# 24V.net
KiCad netlist of a schematic drawn in Altium Designer
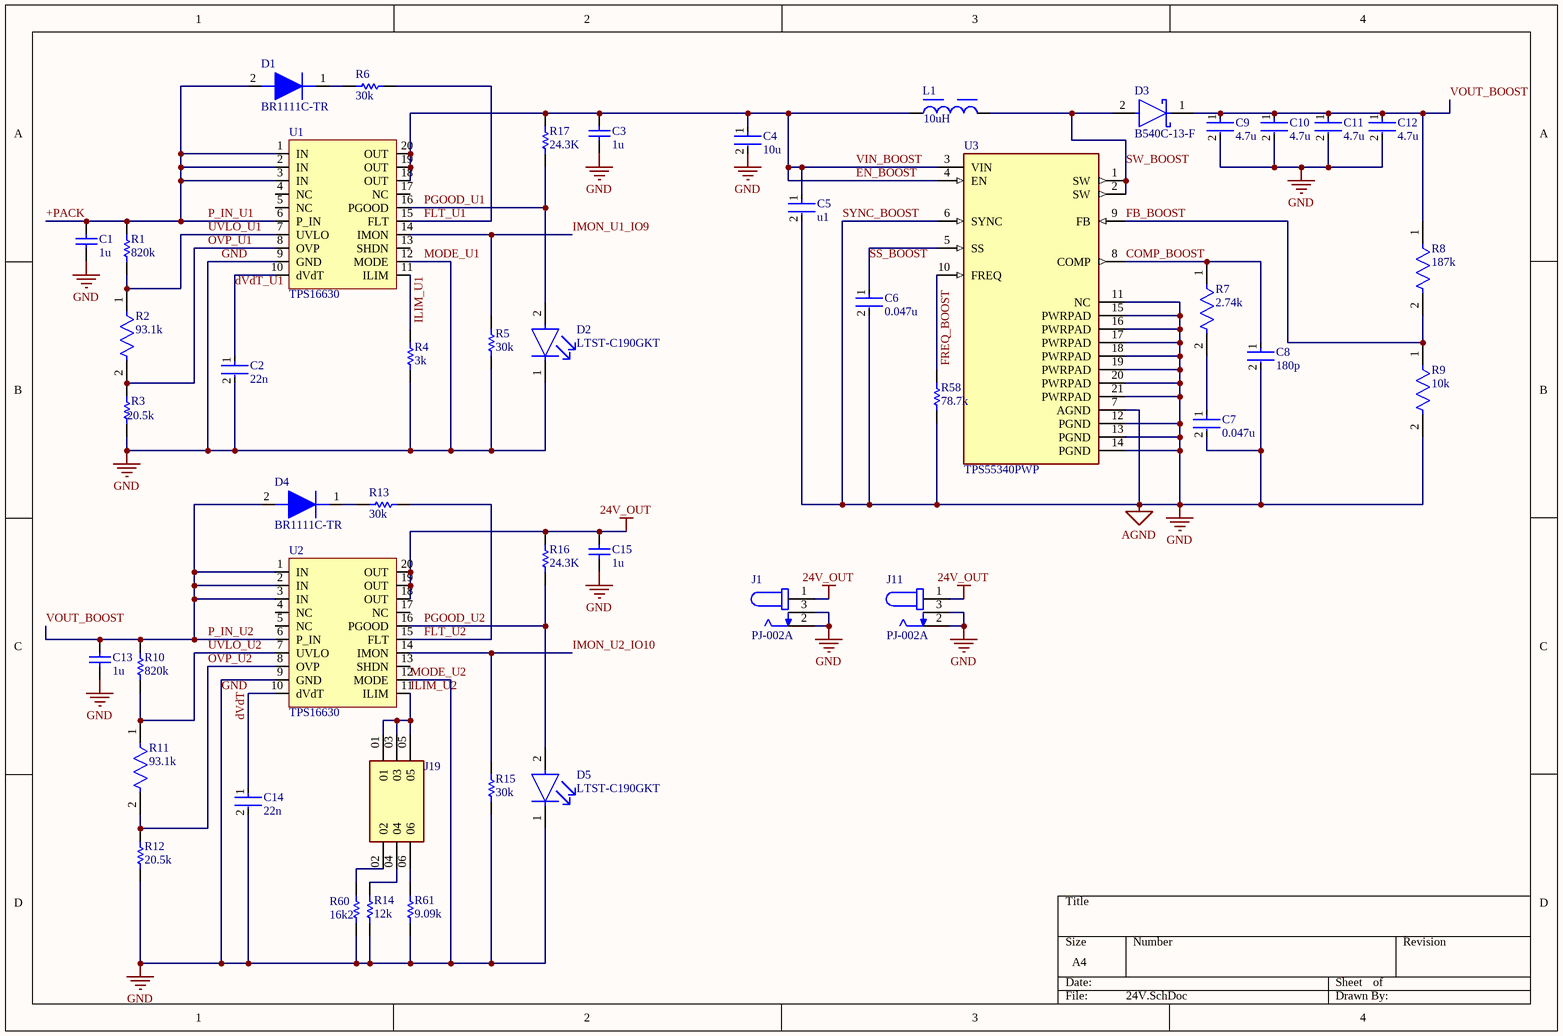
[diagram p0: 24V.SchDoc]

(export (version "E")
  (design (tool "Eeschema 10.0.6"))
  (components
    (comp (ref "C1")
      (value "1u")
      (footprint "CAPC2013X140X50ML20T25")
      (fields (field (name "MANUFACTURER") "Kemet") (field (name "PART NUMBER") "C0805C105K5RACTU"))
      (libsource (lib "Altium Content Vault") (part "CAP"))
    )
    (comp (ref "C2")
      (value "22n")
      (footprint "FP-C0603C-CF-MFG")
      (description "Ceramic Capacitor 0.022Uf 16V, X7R, 10%, 0603, Full Reel")
      (fields
        (field (name "OCTOPART") "https://octopart.com/c0603c223k4ractu-kemet-123286")
        (field (name "MANUFACTURER PART NUMBER") "C0603C223K4RACTU")
      )
      (libsource (lib "Altium Content Vault") (part "b4654b650e69147ec39a6b967a45e02"))
    )
    (comp (ref "C3")
      (value "1u")
      (footprint "CAPC2013X140X50ML20T25")
      (fields (field (name "MANUFACTURER") "Kemet") (field (name "PART NUMBER") "C0805C105K5RACTU"))
      (libsource (lib "Altium Content Vault") (part "CAP"))
    )
    (comp (ref "C4")
      (value "10u")
      (footprint "FP-GRM21B-0_2-e0_2_0_7-MFG")
      (libsource (lib "Altium Content Vault") (part "b4654b650e69147ec39a6b967a45e02"))
    )
    (comp (ref "C5")
      (value "u1")
      (footprint "FP-CC0805-0_85-MFG")
      (description "CC0805KRX7R9BB104 CAP CER 0.1UF 50V X7R 0805")
      (fields (field (name "TOLERANCE") "0.1") (field (name "MANUFACTURER PART NUMBER") "CC0805KRX7R9BB104"))
      (libsource (lib "Altium Content Vault") (part "11868f565c42a9108669ba33697ecf6"))
    )
    (comp (ref "C6")
      (value "0.047u")
      (footprint "FP-C0805C-DN-MFG")
      (description "C0805C473K5RACTU  CAP CER 0.047UF 50V X7R 0805")
      (fields
        (field (name "MANUFACTURER PART NUMBER") "C0805C473K5RACTU")
        (field (name "OCTOPART") "https://octopart.com/c0805c473k5ractu-kemet-138387")
      )
      (libsource (lib "Altium Content Vault") (part "b4654b650e69147ec39a6b967a45e02"))
    )
    (comp (ref "C7")
      (value "0.047u")
      (footprint "FP-C0805C-DN-MFG")
      (description "C0805C473K5RACTU  CAP CER 0.047UF 50V X7R 0805")
      (fields
        (field (name "MANUFACTURER PART NUMBER") "C0805C473K5RACTU")
        (field (name "OCTOPART") "https://octopart.com/c0805c473k5ractu-kemet-138387")
      )
      (libsource (lib "Altium Content Vault") (part "b4654b650e69147ec39a6b967a45e02"))
    )
    (comp (ref "C8")
      (value "180p")
      (footprint "FP-C0805C-DN-MFG")
      (description "CAP CER 180PF 50V C0G/NP0 0805")
      (fields
        (field (name "MANUFACTURER") "KEMET")
        (field (name "OCTOPART") "https://octopart.com/c0805c181j5gactu-kemet-108653")
      )
      (libsource (lib "Altium Content Vault") (part "b4654b650e69147ec39a6b967a45e02"))
    )
    (comp (ref "C9")
      (value "4.7u")
      (footprint "FP-GRM32-MFG")
      (description "CAP CER 4.7UF 50V X7R 1210")
      (fields (field (name "MANUFACTURER") "Murata") (field (name "TOLERANCE") "10%"))
      (libsource (lib "Altium Content Vault") (part "b4654b650e69147ec39a6b967a45e02"))
    )
    (comp (ref "C10")
      (value "4.7u")
      (footprint "FP-GRM32-MFG")
      (description "CAP CER 4.7UF 50V X7R 1210")
      (fields (field (name "MANUFACTURER") "Murata") (field (name "TOLERANCE") "10%"))
      (libsource (lib "Altium Content Vault") (part "b4654b650e69147ec39a6b967a45e02"))
    )
    (comp (ref "C11")
      (value "4.7u")
      (footprint "FP-GRM32-MFG")
      (description "CAP CER 4.7UF 50V X7R 1210")
      (fields (field (name "MANUFACTURER") "Murata") (field (name "TOLERANCE") "10%"))
      (libsource (lib "Altium Content Vault") (part "b4654b650e69147ec39a6b967a45e02"))
    )
    (comp (ref "C12")
      (value "4.7u")
      (footprint "FP-GRM32-MFG")
      (description "CAP CER 4.7UF 50V X7R 1210")
      (fields (field (name "MANUFACTURER") "Murata") (field (name "TOLERANCE") "10%"))
      (libsource (lib "Altium Content Vault") (part "b4654b650e69147ec39a6b967a45e02"))
    )
    (comp (ref "C13")
      (value "1u")
      (footprint "CAPC2013X140X50ML20T25")
      (fields (field (name "MANUFACTURER") "Kemet") (field (name "PART NUMBER") "C0805C105K5RACTU"))
      (libsource (lib "Altium Content Vault") (part "CAP"))
    )
    (comp (ref "C14")
      (value "22n")
      (footprint "FP-C0603C-CF-MFG")
      (description "Ceramic Capacitor 0.022Uf 16V, X7R, 10%, 0603, Full Reel")
      (fields
        (field (name "OCTOPART") "https://octopart.com/c0603c223k4ractu-kemet-123286")
        (field (name "MANUFACTURER PART NUMBER") "C0603C223K4RACTU")
      )
      (libsource (lib "Altium Content Vault") (part "b4654b650e69147ec39a6b967a45e02"))
    )
    (comp (ref "C15")
      (value "1u")
      (footprint "CAPC2013X140X50ML20T25")
      (fields (field (name "MANUFACTURER") "Kemet") (field (name "PART NUMBER") "C0805C105K5RACTU"))
      (libsource (lib "Altium Content Vault") (part "CAP"))
    )
    (comp (ref "D1")
      (value "BR1111C-TR")
      (footprint "LED_APHD1608LVBC/D")
      (libsource (lib "PowerDistribution") (part "BR1111C-TR"))
    )
    (comp (ref "D2")
      (value "LTST-C190GKT")
      (footprint "FP-LTST-C190GKT-MFG")
      (description "LED GREEN CLEAR CHIP SMD")
      (fields (field (name "VOLTAGE") "2V"))
      (libsource (lib "Altium Content Vault") (part "8706943c75ba83719d021d2fdc84c58"))
    )
    (comp (ref "D3")
      (value "B540C-13-F")
      (footprint "FP-SMC-MFG")
      (description "DIODE SCHOTTKY 40V 5A SMC")
      (fields
        (field (name "OCTOPART") "https://octopart.com/b540c-13-f-diodes+inc.-325873")
        (field (name "MANUFACTURER") "Diodes Inc.")
      )
      (libsource (lib "Altium Content Vault") (part "1d6ec82d83fb6aee721767c19dac4b9"))
    )
    (comp (ref "D4")
      (value "BR1111C-TR")
      (footprint "LED_APHD1608LVBC/D")
      (libsource (lib "PowerDistribution") (part "BR1111C-TR"))
    )
    (comp (ref "D5")
      (value "LTST-C190GKT")
      (footprint "FP-LTST-C190GKT-MFG")
      (description "LED GREEN CLEAR CHIP SMD")
      (fields (field (name "VOLTAGE") "2V"))
      (libsource (lib "Altium Content Vault") (part "8706943c75ba83719d021d2fdc84c58"))
    )
    (comp (ref "J1")
      (value "PJ-002A")
      (footprint "CUI_PJ-002A")
      (description "2.0 x 6.5 mm, 2.5 A, Horizontal, Through Hole, Dc Power Jack Connector")
      (fields (field (name "MF") "CUI Devices"))
      (libsource (lib "PowerDistribution") (part "PJ-002A"))
    )
    (comp (ref "J11")
      (value "PJ-002A")
      (footprint "CUI_PJ-002A")
      (description "2.0 x 6.5 mm, 2.5 A, Horizontal, Through Hole, Dc Power Jack Connector")
      (fields (field (name "MF") "CUI Devices"))
      (libsource (lib "PowerDistribution") (part "PJ-002A"))
    )
    (comp (ref "J19")
      (value "MTSW-103-10-T-D-470")
      (footprint "SAMTEC_MTSW-103-10-T-D-470")
      (libsource (lib "PowerDistribution") (part "MTSW-103-10-T-D-470"))
    )
    (comp (ref "L1")
      (value "10uH")
      (footprint "WE-LHMI_1040")
      (fields (field (name "TOLERANCE") "20%"))
      (libsource (lib "Altium Content Vault") (part "Inductor - 3"))
    )
    (comp (ref "R1")
      (value "820k")
      (footprint "RESC1608X55X30ML15T15")
      (fields (field (name "MANUFACTURER") "Panasonic") (field (name "PART NUMBER") "ERJ3EKF8203V"))
      (libsource (lib "Altium Content Vault") (part "RES"))
    )
    (comp (ref "R2")
      (value "93.1k")
      (footprint "FP-CR0805-IPC_B")
      (description "Thick Film Chip Resistors 0805 93.1kΩ 0.125W 1% 100ppm/°C")
      (fields (field (name "TOLERANCE") "1%"))
      (libsource (lib "Altium Content Vault") (part "1029c3af85768c4190bb7ad29bc67b5"))
    )
    (comp (ref "R3")
      (value "20.5k")
      (footprint "RESC2013X60X40LL20T25")
      (fields (field (name "MANUFACTURER") "Panasonic") (field (name "PART NUMBER") "ERA6AEB2052V"))
      (libsource (lib "Altium Content Vault") (part "RES"))
    )
    (comp (ref "R4")
      (value "3k")
      (footprint "RESC2013X70X40NL20T20")
      (description "ERJ-6GEYJ302V")
      (fields (field (name "MANUFACTURER") "Panasonic"))
      (libsource (lib "Altium Content Vault") (part "RES"))
    )
    (comp (ref "R5")
      (value "30k")
      (footprint "RESC1609X50X30ML10T20")
      (fields (field (name "MANUFACTURER") "Vishay Dale") (field (name "PART NUMBER") "CRCW060330K0JNEA"))
      (libsource (lib "Altium Content Vault") (part "RES"))
    )
    (comp (ref "R6")
      (value "30k")
      (footprint "RESC1609X50X30ML10T20")
      (fields (field (name "MANUFACTURER") "Vishay Dale") (field (name "PART NUMBER") "CRCW060330K0JNEA"))
      (libsource (lib "Altium Content Vault") (part "RES"))
    )
    (comp (ref "R7")
      (value "2.74k")
      (footprint "FP-CR0805-IPC_A")
      (description "Thick Film Chip Resistors 0805 2.74kΩ 0.125W 1% 100ppm/°C")
      (fields (field (name "TOLERANCE") "1%"))
      (libsource (lib "Altium Content Vault") (part "1029c3af85768c4190bb7ad29bc67b5"))
    )
    (comp (ref "R8")
      (value "187k")
      (footprint "FP-ERJ3EK-MFG")
      (description "RES SMD 187K OHM 1% 1/10W 0603")
      (fields (field (name "TOLERANCE") "1%"))
      (libsource (lib "Altium Content Vault") (part "1029c3af85768c4190bb7ad29bc67b5"))
    )
    (comp (ref "R9")
      (value "10k")
      (footprint "FP-ERA3A-IPC_C")
      (description "RES SMD 10K OHM 0.1% 1/10W 0603")
      (fields (field (name "TOLERANCE") "0.1%"))
      (libsource (lib "Altium Content Vault") (part "4e5f8b3dd332802e91518312df5df73"))
    )
    (comp (ref "R10")
      (value "820k")
      (footprint "RESC1608X55X30ML15T15")
      (fields (field (name "MANUFACTURER") "Panasonic") (field (name "PART NUMBER") "ERJ3EKF8203V"))
      (libsource (lib "Altium Content Vault") (part "RES"))
    )
    (comp (ref "R11")
      (value "93.1k")
      (footprint "FP-CR0805-IPC_B")
      (description "Thick Film Chip Resistors 0805 93.1kΩ 0.125W 1% 100ppm/°C")
      (fields (field (name "TOLERANCE") "1%"))
      (libsource (lib "Altium Content Vault") (part "1029c3af85768c4190bb7ad29bc67b5"))
    )
    (comp (ref "R12")
      (value "20.5k")
      (footprint "RESC2013X60X40LL20T25")
      (fields (field (name "MANUFACTURER") "Panasonic") (field (name "PART NUMBER") "ERA6AEB2052V"))
      (libsource (lib "Altium Content Vault") (part "RES"))
    )
    (comp (ref "R13")
      (value "30k")
      (footprint "RESC1609X50X30ML10T20")
      (fields (field (name "MANUFACTURER") "Vishay Dale") (field (name "PART NUMBER") "CRCW060330K0JNEA"))
      (libsource (lib "Altium Content Vault") (part "RES"))
    )
    (comp (ref "R14")
      (value "12k")
      (footprint "RESC2013X70X40ML20T20")
      (fields (field (name "MANUFACTURER") "Panasonic") (field (name "PART NUMBER") "ERJ6ENF1202V"))
      (libsource (lib "Altium Content Vault") (part "RES"))
    )
    (comp (ref "R15")
      (value "30k")
      (footprint "RESC1609X50X30ML10T20")
      (fields (field (name "MANUFACTURER") "Vishay Dale") (field (name "PART NUMBER") "CRCW060330K0JNEA"))
      (libsource (lib "Altium Content Vault") (part "RES"))
    )
    (comp (ref "R16")
      (value "24.3K")
      (footprint "RESC1609X50X30NL10T20")
      (fields (field (name "PART NUMBER") "CRCW060324K3FKEA") (field (name "MANUFACTURER") "Vishay Dale"))
      (libsource (lib "Altium Content Vault") (part "RES"))
    )
    (comp (ref "R17")
      (value "24.3K")
      (footprint "RESC1609X50X30NL10T20")
      (fields (field (name "PART NUMBER") "CRCW060324K3FKEA") (field (name "MANUFACTURER") "Vishay Dale"))
      (libsource (lib "Altium Content Vault") (part "RES"))
    )
    (comp (ref "R58")
      (value "78.7k")
      (footprint "RESC1608X55X30ML15T15")
      (fields (field (name "PART NUMBER") "ERJ-3EKF7872V") (field (name "MANUFACTURER") "Panasonic"))
      (libsource (lib "Altium Content Vault") (part "RES"))
    )
    (comp (ref "R60")
      (value "16k2")
      (footprint "RESC2013X50X30NL20T20")
      (description "CRCW080516K2FKEA")
      (fields (field (name "MANUFACTURER") "Vishay Dale"))
      (libsource (lib "Altium Content Vault") (part "RES"))
    )
    (comp (ref "R61")
      (value "9.09k")
      (footprint "RESC2013X60X35ML10T20")
      (fields (field (name "TOLERANCE") "1%"))
      (libsource (lib "Altium Content Vault") (part "RES-2"))
    )
    (comp (ref "U1")
      (value "TPS16630")
      (footprint "SOP65P640X110-21N")
      (libsource (lib "PowerDistribution") (part "TPS16630"))
    )
    (comp (ref "U2")
      (value "TPS16630")
      (footprint "SOP65P640X110-21N")
      (libsource (lib "PowerDistribution") (part "TPS16630"))
    )
    (comp (ref "U3")
      (value "TPS55340PWP")
      (footprint "IC_TPS55340PWP")
      (description "Integrated, 5-A 40-V Wide Input Range Boost/SEPIC/Flyback DC-DC Regulator 14-HTSSOP -40 to 150")
      (fields (field (name "MF") "Texas Instruments"))
      (libsource (lib "PowerDistribution") (part "TPS55340PWP"))
    )
  )
  (nets
    (net (code "1") (name "/+PACK") (class "Default")
      (node (ref "C1") (pin "2") (pinfunction "2_2") (pintype "passive"))
      (node (ref "D1") (pin "2") (pinfunction "2_2") (pintype "passive"))
      (node (ref "R1") (pin "2") (pinfunction "2_2") (pintype "passive"))
      (node (ref "U1") (pin "1") (pinfunction "IN_1") (pintype "passive"))
      (node (ref "U1") (pin "2") (pinfunction "IN_2") (pintype "passive"))
      (node (ref "U1") (pin "3") (pinfunction "IN_3") (pintype "passive"))
      (node (ref "U1") (pin "6") (pinfunction "P_IN_6") (pintype "passive"))
    )
    (net (code "2") (name "/COMP_BOOST") (class "Default")
      (node (ref "C8") (pin "1") (pinfunction "1_1") (pintype "passive"))
      (node (ref "R7") (pin "1") (pinfunction "1_1") (pintype "passive"))
      (node (ref "U3") (pin "8") (pinfunction "COMP_8") (pintype "output"))
    )
    (net (code "3") (name "/EN_BOOST") (class "Default")
      (node (ref "C3") (pin "2") (pinfunction "2_2") (pintype "passive"))
      (node (ref "C4") (pin "1") (pinfunction "1_1") (pintype "passive"))
      (node (ref "C5") (pin "1") (pinfunction "1_1") (pintype "passive"))
      (node (ref "L1") (pin "1") (pinfunction "1_1") (pintype "passive"))
      (node (ref "R17") (pin "2") (pinfunction "2_2") (pintype "passive"))
      (node (ref "U1") (pin "18") (pinfunction "OUT_18") (pintype "passive"))
      (node (ref "U1") (pin "19") (pinfunction "OUT_19") (pintype "passive"))
      (node (ref "U1") (pin "20") (pinfunction "OUT_20") (pintype "passive"))
      (node (ref "U3") (pin "3") (pinfunction "VIN_3") (pintype "power_in"))
      (node (ref "U3") (pin "4") (pinfunction "EN_4") (pintype "input"))
    )
    (net (code "4") (name "/FB_BOOST") (class "Default")
      (node (ref "R8") (pin "2") (pinfunction "2_2") (pintype "passive"))
      (node (ref "R9") (pin "1") (pinfunction "1_1") (pintype "passive"))
      (node (ref "U3") (pin "9") (pinfunction "FB_9") (pintype "input"))
    )
    (net (code "5") (name "/FLT_U1") (class "Default")
      (node (ref "R6") (pin "1") (pinfunction "1_1") (pintype "passive"))
      (node (ref "U1") (pin "15") (pinfunction "FLT_15") (pintype "passive"))
    )
    (net (code "6") (name "/FLT_U2") (class "Default")
      (node (ref "R13") (pin "2") (pinfunction "2_2") (pintype "passive"))
      (node (ref "U2") (pin "15") (pinfunction "FLT_15") (pintype "passive"))
    )
    (net (code "7") (name "/FREQ_BOOST") (class "Default")
      (node (ref "R58") (pin "2") (pinfunction "2_2") (pintype "passive"))
      (node (ref "U3") (pin "10") (pinfunction "FREQ_10") (pintype "input"))
    )
    (net (code "8") (name "/ILIM_U1") (class "Default")
      (node (ref "R4") (pin "2") (pinfunction "2_2") (pintype "passive"))
      (node (ref "U1") (pin "11") (pinfunction "ILIM_11") (pintype "passive"))
    )
    (net (code "9") (name "/ILIM_U2") (class "Default")
      (node (ref "J19") (pin "01") (pinfunction "01_01") (pintype "passive"))
      (node (ref "J19") (pin "03") (pinfunction "03_03") (pintype "passive"))
      (node (ref "J19") (pin "05") (pinfunction "05_05") (pintype "passive"))
      (node (ref "U2") (pin "11") (pinfunction "ILIM_11") (pintype "passive"))
    )
    (net (code "10") (name "/IMON_U1_IO9") (class "Default")
      (node (ref "R5") (pin "2") (pinfunction "2_2") (pintype "passive"))
      (node (ref "U1") (pin "14") (pinfunction "IMON_14") (pintype "passive"))
    )
    (net (code "11") (name "/IMON_U2_IO10") (class "Default")
      (node (ref "R15") (pin "2") (pinfunction "2_2") (pintype "passive"))
      (node (ref "U2") (pin "14") (pinfunction "IMON_14") (pintype "passive"))
    )
    (net (code "12") (name "/OVP_U1") (class "Default")
      (node (ref "R2") (pin "2") (pinfunction "2_2") (pintype "passive"))
      (node (ref "R3") (pin "2") (pinfunction "2_2") (pintype "passive"))
      (node (ref "U1") (pin "8") (pinfunction "OVP_8") (pintype "passive"))
    )
    (net (code "13") (name "/OVP_U2") (class "Default")
      (node (ref "R11") (pin "2") (pinfunction "2_2") (pintype "passive"))
      (node (ref "R12") (pin "2") (pinfunction "2_2") (pintype "passive"))
      (node (ref "U2") (pin "8") (pinfunction "OVP_8") (pintype "passive"))
    )
    (net (code "14") (name "/PGOOD_U1") (class "Default")
      (node (ref "D2") (pin "2") (pinfunction "A_2") (pintype "passive"))
      (node (ref "R17") (pin "1") (pinfunction "1_1") (pintype "passive"))
      (node (ref "U1") (pin "16") (pinfunction "PGOOD_16") (pintype "passive"))
    )
    (net (code "15") (name "/PGOOD_U2") (class "Default")
      (node (ref "D5") (pin "2") (pinfunction "A_2") (pintype "passive"))
      (node (ref "R16") (pin "1") (pinfunction "1_1") (pintype "passive"))
      (node (ref "U2") (pin "16") (pinfunction "PGOOD_16") (pintype "passive"))
    )
    (net (code "16") (name "/P_IN_U2") (class "Default")
      (node (ref "C10") (pin "1") (pinfunction "1_1") (pintype "passive"))
      (node (ref "C11") (pin "1") (pinfunction "1_1") (pintype "passive"))
      (node (ref "C12") (pin "1") (pinfunction "1_1") (pintype "passive"))
      (node (ref "C13") (pin "2") (pinfunction "2_2") (pintype "passive"))
      (node (ref "C9") (pin "1") (pinfunction "1_1") (pintype "passive"))
      (node (ref "D3") (pin "1") (pinfunction "C_1") (pintype "passive"))
      (node (ref "D4") (pin "2") (pinfunction "2_2") (pintype "passive"))
      (node (ref "R10") (pin "2") (pinfunction "2_2") (pintype "passive"))
      (node (ref "R8") (pin "1") (pinfunction "1_1") (pintype "passive"))
      (node (ref "U2") (pin "1") (pinfunction "IN_1") (pintype "passive"))
      (node (ref "U2") (pin "2") (pinfunction "IN_2") (pintype "passive"))
      (node (ref "U2") (pin "3") (pinfunction "IN_3") (pintype "passive"))
      (node (ref "U2") (pin "6") (pinfunction "P_IN_6") (pintype "passive"))
    )
    (net (code "17") (name "/SS_BOOST") (class "Default")
      (node (ref "C6") (pin "1") (pinfunction "1_1") (pintype "passive"))
      (node (ref "U3") (pin "5") (pinfunction "SS_5") (pintype "input"))
    )
    (net (code "18") (name "/SW_BOOST") (class "Default")
      (node (ref "D3") (pin "2") (pinfunction "A_2") (pintype "passive"))
      (node (ref "L1") (pin "2") (pinfunction "2_2") (pintype "passive"))
      (node (ref "U3") (pin "1") (pinfunction "SW_1") (pintype "output"))
      (node (ref "U3") (pin "2") (pinfunction "SW_2") (pintype "output"))
    )
    (net (code "19") (name "/UVLO_U1") (class "Default")
      (node (ref "R1") (pin "1") (pinfunction "1_1") (pintype "passive"))
      (node (ref "R2") (pin "1") (pinfunction "1_1") (pintype "passive"))
      (node (ref "U1") (pin "7") (pinfunction "UVLO_7") (pintype "passive"))
    )
    (net (code "20") (name "/UVLO_U2") (class "Default")
      (node (ref "R10") (pin "1") (pinfunction "1_1") (pintype "passive"))
      (node (ref "R11") (pin "1") (pinfunction "1_1") (pintype "passive"))
      (node (ref "U2") (pin "7") (pinfunction "UVLO_7") (pintype "passive"))
    )
    (net (code "21") (name "/dVdT") (class "Default")
      (node (ref "C14") (pin "1") (pinfunction "1_1") (pintype "passive"))
      (node (ref "U2") (pin "10") (pinfunction "dVdT_10") (pintype "passive"))
    )
    (net (code "22") (name "/dVdT_U1") (class "Default")
      (node (ref "C2") (pin "1") (pinfunction "1_1") (pintype "passive"))
      (node (ref "U1") (pin "10") (pinfunction "dVdT_10") (pintype "passive"))
    )
    (net (code "23") (name "24V_OUT") (class "Default")
      (node (ref "C15") (pin "2") (pinfunction "2_2") (pintype "passive"))
      (node (ref "J1") (pin "1") (pinfunction "1_1") (pintype "passive"))
      (node (ref "J11") (pin "1") (pinfunction "1_1") (pintype "passive"))
      (node (ref "R16") (pin "2") (pinfunction "2_2") (pintype "passive"))
      (node (ref "U2") (pin "18") (pinfunction "OUT_18") (pintype "passive"))
      (node (ref "U2") (pin "19") (pinfunction "OUT_19") (pintype "passive"))
      (node (ref "U2") (pin "20") (pinfunction "OUT_20") (pintype "passive"))
    )
    (net (code "24") (name "AGND") (class "Default")
      (node (ref "C1") (pin "1") (pinfunction "1_1") (pintype "passive"))
      (node (ref "C10") (pin "2") (pinfunction "2_2") (pintype "passive"))
      (node (ref "C11") (pin "2") (pinfunction "2_2") (pintype "passive"))
      (node (ref "C12") (pin "2") (pinfunction "2_2") (pintype "passive"))
      (node (ref "C13") (pin "1") (pinfunction "1_1") (pintype "passive"))
      (node (ref "C14") (pin "2") (pinfunction "2_2") (pintype "passive"))
      (node (ref "C15") (pin "1") (pinfunction "1_1") (pintype "passive"))
      (node (ref "C2") (pin "2") (pinfunction "2_2") (pintype "passive"))
      (node (ref "C3") (pin "1") (pinfunction "1_1") (pintype "passive"))
      (node (ref "C4") (pin "2") (pinfunction "2_2") (pintype "passive"))
      (node (ref "C5") (pin "2") (pinfunction "2_2") (pintype "passive"))
      (node (ref "C6") (pin "2") (pinfunction "2_2") (pintype "passive"))
      (node (ref "C7") (pin "2") (pinfunction "2_2") (pintype "passive"))
      (node (ref "C8") (pin "2") (pinfunction "2_2") (pintype "passive"))
      (node (ref "C9") (pin "2") (pinfunction "2_2") (pintype "passive"))
      (node (ref "D2") (pin "1") (pinfunction "C_1") (pintype "passive"))
      (node (ref "D5") (pin "1") (pinfunction "C_1") (pintype "passive"))
      (node (ref "J1") (pin "2") (pinfunction "2_2") (pintype "passive"))
      (node (ref "J1") (pin "3") (pinfunction "3_3") (pintype "passive"))
      (node (ref "J11") (pin "2") (pinfunction "2_2") (pintype "passive"))
      (node (ref "J11") (pin "3") (pinfunction "3_3") (pintype "passive"))
      (node (ref "R12") (pin "1") (pinfunction "1_1") (pintype "passive"))
      (node (ref "R14") (pin "1") (pinfunction "1_1") (pintype "passive"))
      (node (ref "R15") (pin "1") (pinfunction "1_1") (pintype "passive"))
      (node (ref "R3") (pin "1") (pinfunction "1_1") (pintype "passive"))
      (node (ref "R4") (pin "1") (pinfunction "1_1") (pintype "passive"))
      (node (ref "R5") (pin "1") (pinfunction "1_1") (pintype "passive"))
      (node (ref "R58") (pin "1") (pinfunction "1_1") (pintype "passive"))
      (node (ref "R60") (pin "1") (pinfunction "1_1") (pintype "passive"))
      (node (ref "R61") (pin "1") (pinfunction "1_1") (pintype "passive"))
      (node (ref "R9") (pin "2") (pinfunction "2_2") (pintype "passive"))
      (node (ref "U1") (pin "12") (pinfunction "MODE_12") (pintype "passive"))
      (node (ref "U1") (pin "9") (pinfunction "GND_9") (pintype "passive"))
      (node (ref "U2") (pin "12") (pinfunction "MODE_12") (pintype "passive"))
      (node (ref "U2") (pin "9") (pinfunction "GND_9") (pintype "passive"))
      (node (ref "U3") (pin "11") (pinfunction "NC_11") (pintype "power_in"))
      (node (ref "U3") (pin "12") (pinfunction "PGND_12") (pintype "power_in"))
      (node (ref "U3") (pin "13") (pinfunction "PGND_13") (pintype "power_in"))
      (node (ref "U3") (pin "14") (pinfunction "PGND_14") (pintype "power_in"))
      (node (ref "U3") (pin "15") (pinfunction "PWRPAD_15") (pintype "power_in"))
      (node (ref "U3") (pin "16") (pinfunction "PWRPAD_16") (pintype "power_in"))
      (node (ref "U3") (pin "17") (pinfunction "PWRPAD_17") (pintype "power_in"))
      (node (ref "U3") (pin "18") (pinfunction "PWRPAD_18") (pintype "power_in"))
      (node (ref "U3") (pin "19") (pinfunction "PWRPAD_19") (pintype "power_in"))
      (node (ref "U3") (pin "20") (pinfunction "PWRPAD_20") (pintype "power_in"))
      (node (ref "U3") (pin "21") (pinfunction "PWRPAD_21") (pintype "power_in"))
      (node (ref "U3") (pin "6") (pinfunction "SYNC_6") (pintype "input"))
      (node (ref "U3") (pin "7") (pinfunction "AGND_7") (pintype "power_in"))
    )
    (net (code "25") (name "Net-(C7-Pad1)") (class "Default")
      (node (ref "C7") (pin "1") (pinfunction "1_1") (pintype "passive"))
      (node (ref "R7") (pin "2") (pinfunction "2_2") (pintype "passive"))
    )
    (net (code "26") (name "Net-(D1-Pad1)") (class "Default")
      (node (ref "D1") (pin "1") (pinfunction "1_1") (pintype "passive"))
      (node (ref "R6") (pin "2") (pinfunction "2_2") (pintype "passive"))
    )
    (net (code "27") (name "Net-(D4-Pad1)") (class "Default")
      (node (ref "D4") (pin "1") (pinfunction "1_1") (pintype "passive"))
      (node (ref "R13") (pin "1") (pinfunction "1_1") (pintype "passive"))
    )
    (net (code "28") (name "Net-(J19-Pad02)") (class "Default")
      (node (ref "J19") (pin "02") (pinfunction "02_02") (pintype "passive"))
      (node (ref "R60") (pin "2") (pinfunction "2_2") (pintype "passive"))
    )
    (net (code "29") (name "Net-(J19-Pad04)") (class "Default")
      (node (ref "J19") (pin "04") (pinfunction "04_04") (pintype "passive"))
      (node (ref "R14") (pin "2") (pinfunction "2_2") (pintype "passive"))
    )
    (net (code "30") (name "Net-(J19-Pad06)") (class "Default")
      (node (ref "J19") (pin "06") (pinfunction "06_06") (pintype "passive"))
      (node (ref "R61") (pin "2") (pinfunction "2_2") (pintype "passive"))
    )
    (net (code "31") (name "unconnected-(U1-NC-Pad4)") (class "Default")
      (node (ref "U1") (pin "4") (pinfunction "NC_4") (pintype "passive"))
    )
    (net (code "32") (name "unconnected-(U1-NC-Pad5)") (class "Default")
      (node (ref "U1") (pin "5") (pinfunction "NC_5") (pintype "passive"))
    )
    (net (code "33") (name "unconnected-(U1-NC-Pad17)") (class "Default")
      (node (ref "U1") (pin "17") (pinfunction "NC_17") (pintype "passive"))
    )
    (net (code "34") (name "unconnected-(U1-SHDN-Pad13)") (class "Default")
      (node (ref "U1") (pin "13") (pinfunction "SHDN_13") (pintype "passive"))
    )
    (net (code "35") (name "unconnected-(U2-NC-Pad4)") (class "Default")
      (node (ref "U2") (pin "4") (pinfunction "NC_4") (pintype "passive"))
    )
    (net (code "36") (name "unconnected-(U2-NC-Pad5)") (class "Default")
      (node (ref "U2") (pin "5") (pinfunction "NC_5") (pintype "passive"))
    )
    (net (code "37") (name "unconnected-(U2-NC-Pad17)") (class "Default")
      (node (ref "U2") (pin "17") (pinfunction "NC_17") (pintype "passive"))
    )
    (net (code "38") (name "unconnected-(U2-SHDN-Pad13)") (class "Default")
      (node (ref "U2") (pin "13") (pinfunction "SHDN_13") (pintype "passive"))
    )
  )
)
